# neojoint1a-090.net
KiCad netlist of a schematic drawn in EAGLE
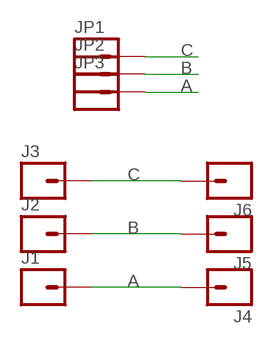
[diagram p0: schematic, sheet 1]

(export (version "E")
  (design (tool "Eeschema 10.0.6"))
  (components
    (comp (ref "J1")
      (value "M01SMD-4.5X1.5")
      (footprint "eagle-import:PAD-1.5X4.5")
      (libsource (lib "eagle-import") (part "M01SMD-4.5X1.5"))
    )
    (comp (ref "J2")
      (value "M01SMD-4.5X1.5")
      (footprint "eagle-import:PAD-1.5X4.5")
      (libsource (lib "eagle-import") (part "M01SMD-4.5X1.5"))
    )
    (comp (ref "J3")
      (value "M01SMD-4.5X1.5")
      (footprint "eagle-import:PAD-1.5X4.5")
      (libsource (lib "eagle-import") (part "M01SMD-4.5X1.5"))
    )
    (comp (ref "J4")
      (value "M01SMD-4.5X1.5")
      (footprint "eagle-import:PAD-1.5X4.5")
      (libsource (lib "eagle-import") (part "M01SMD-4.5X1.5"))
    )
    (comp (ref "J5")
      (value "M01SMD-4.5X1.5")
      (footprint "eagle-import:PAD-1.5X4.5")
      (libsource (lib "eagle-import") (part "M01SMD-4.5X1.5"))
    )
    (comp (ref "J6")
      (value "M01SMD-4.5X1.5")
      (footprint "eagle-import:PAD-1.5X4.5")
      (libsource (lib "eagle-import") (part "M01SMD-4.5X1.5"))
    )
    (comp (ref "JP1")
      (value "M01PTH")
      (footprint "eagle-import:1X01")
      (libsource (lib "eagle-import") (part "M01PTH"))
    )
    (comp (ref "JP2")
      (value "M01PTH")
      (footprint "eagle-import:1X01")
      (libsource (lib "eagle-import") (part "M01PTH"))
    )
    (comp (ref "JP3")
      (value "M01PTH")
      (footprint "eagle-import:1X01")
      (libsource (lib "eagle-import") (part "M01PTH"))
    )
  )
  (nets
    (net (code "1") (name "/A") (class "Default")
      (node (ref "J1") (pin "P$1") (pinfunction "1_P$1") (pintype "passive"))
      (node (ref "J4") (pin "P$1") (pinfunction "1_P$1") (pintype "passive"))
      (node (ref "JP3") (pin "1") (pinfunction "1_1") (pintype "passive"))
    )
    (net (code "2") (name "/B") (class "Default")
      (node (ref "J2") (pin "P$1") (pinfunction "1_P$1") (pintype "passive"))
      (node (ref "J5") (pin "P$1") (pinfunction "1_P$1") (pintype "passive"))
      (node (ref "JP2") (pin "1") (pinfunction "1_1") (pintype "passive"))
    )
    (net (code "3") (name "/C") (class "Default")
      (node (ref "J3") (pin "P$1") (pinfunction "1_P$1") (pintype "passive"))
      (node (ref "J6") (pin "P$1") (pinfunction "1_P$1") (pintype "passive"))
      (node (ref "JP1") (pin "1") (pinfunction "1_1") (pintype "passive"))
    )
  )
)
